# TC_masterProto_Ard.net
KiCad netlist of a schematic drawn in EAGLE
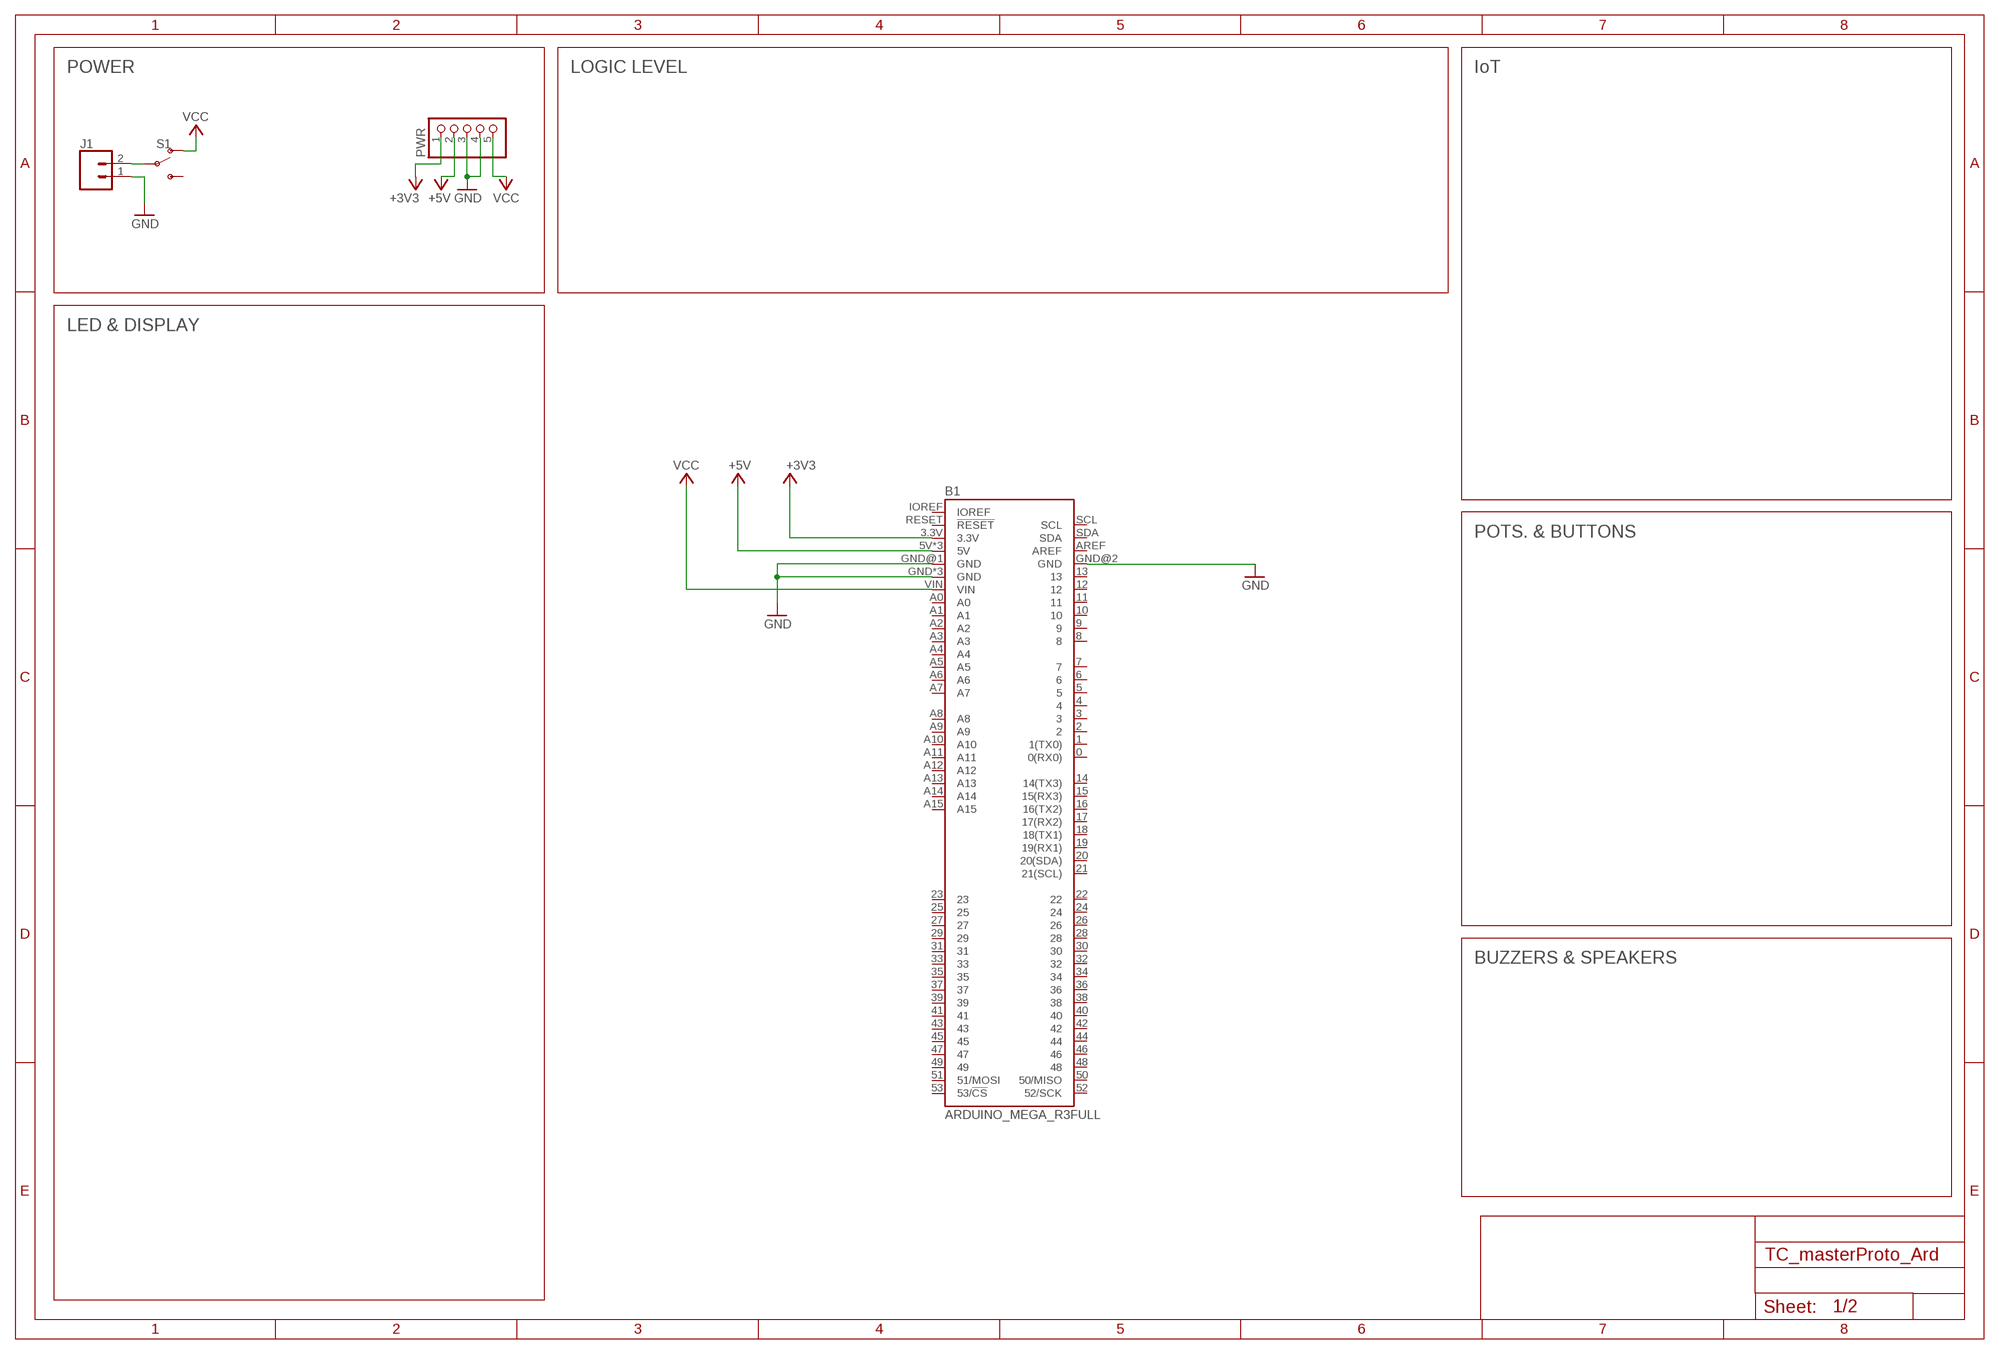
[diagram p0: schematic, sheet 1]
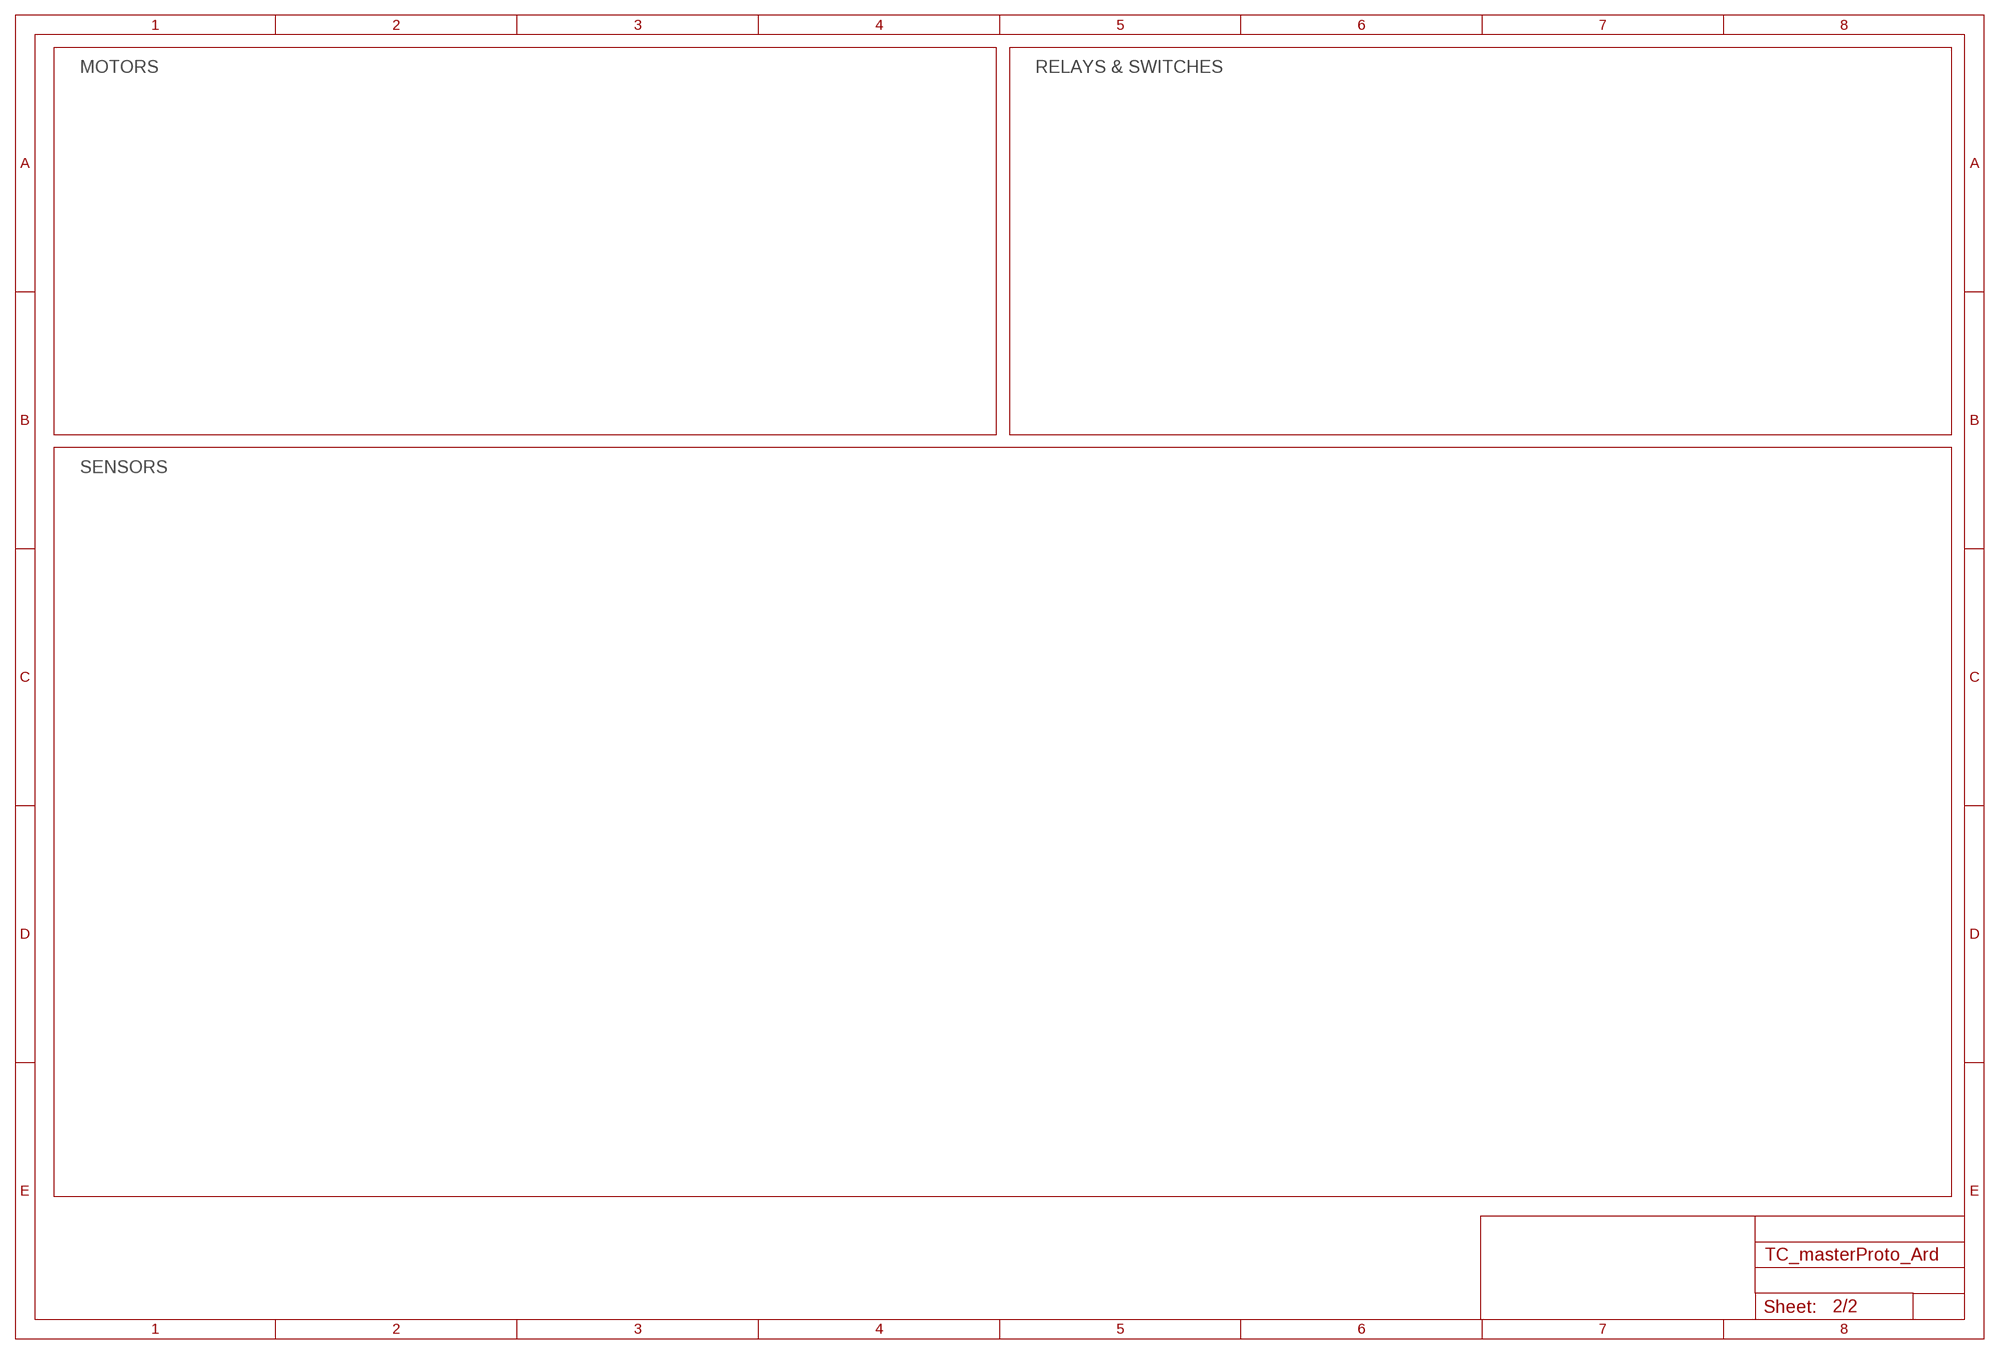
[diagram p1: schematic, sheet 2]

(export (version "E")
  (design (tool "Eeschema 10.0.6"))
  (components
    (comp (ref "B1")
      (value "ARDUINO_MEGA_R3FULL")
      (footprint "eagle-import:ARDUINO_MEGA_NO_SILK")
      (libsource (lib "eagle-import") (part "ARDUINO_MEGA_R3FULL"))
    )
    (comp (ref "J1")
      (value "CONN_023.5MM_LOCK")
      (footprint "eagle-import:SCREWTERMINAL-3.5MM-2_LOCK")
      (libsource (lib "eagle-import") (part "CONN_023.5MM_LOCK"))
    )
    (comp (ref "PWR")
      (value "PINHD-1X5")
      (footprint "eagle-import:1X05")
      (libsource (lib "eagle-import") (part "PINHD-1X5"))
    )
    (comp (ref "S1")
      (value "SWITCH-SPDT-PTH-11.6X4.0MM-LOCK")
      (footprint "eagle-import:SWITCH_SPDT_PTH_11.6X4.0MM_LOCK")
      (libsource (lib "eagle-import") (part "SWITCH-SPDT-PTH-11.6X4.0MM-LOCK"))
    )
  )
  (nets
    (net (code "1") (name "+3V3") (class "Default")
      (node (ref "B1") (pin "3.3V") (pinfunction "3.3V_3.3V") (pintype "bidirectional"))
      (node (ref "PWR") (pin "1") (pinfunction "1_1") (pintype "passive"))
    )
    (net (code "2") (name "+5V") (class "Default")
      (node (ref "B1") (pin "5V") (pinfunction "5V_5V") (pintype "bidirectional"))
      (node (ref "B1") (pin "5V@1") (pinfunction "5V_5V@1") (pintype "bidirectional"))
      (node (ref "B1") (pin "5V@2") (pinfunction "5V_5V@2") (pintype "bidirectional"))
      (node (ref "PWR") (pin "2") (pinfunction "2_2") (pintype "passive"))
    )
    (net (code "3") (name "GND") (class "Default")
      (node (ref "B1") (pin "GND") (pinfunction "GND_GND") (pintype "bidirectional"))
      (node (ref "B1") (pin "GND@1") (pinfunction "GND_GND@1") (pintype "bidirectional"))
      (node (ref "B1") (pin "GND@2") (pinfunction "GND_GND@2") (pintype "bidirectional"))
      (node (ref "B1") (pin "GND@3") (pinfunction "GND_GND@3") (pintype "bidirectional"))
      (node (ref "B1") (pin "GND@4") (pinfunction "GND_GND@4") (pintype "bidirectional"))
      (node (ref "J1") (pin "1") (pinfunction "1_1") (pintype "passive"))
      (node (ref "PWR") (pin "3") (pinfunction "3_3") (pintype "passive"))
      (node (ref "PWR") (pin "4") (pinfunction "4_4") (pintype "passive"))
    )
    (net (code "4") (name "Net-(S1-P)") (class "Default")
      (node (ref "J1") (pin "2") (pinfunction "2_2") (pintype "passive"))
      (node (ref "S1") (pin "2") (pinfunction "P_2") (pintype "passive"))
    )
    (net (code "5") (name "VCC") (class "Default")
      (node (ref "B1") (pin "VIN") (pinfunction "VIN_VIN") (pintype "bidirectional"))
      (node (ref "PWR") (pin "5") (pinfunction "5_5") (pintype "passive"))
      (node (ref "S1") (pin "1") (pinfunction "O_1") (pintype "passive"))
    )
    (net (code "6") (name "unconnected-(B1-0(RX0)-Pad0)") (class "Default")
      (node (ref "B1") (pin "0") (pinfunction "0(RX0)_0") (pintype "bidirectional"))
    )
    (net (code "7") (name "unconnected-(B1-1(TX0)-Pad1)") (class "Default")
      (node (ref "B1") (pin "1") (pinfunction "1(TX0)_1") (pintype "bidirectional"))
    )
    (net (code "8") (name "unconnected-(B1-14(TX3)-Pad14)") (class "Default")
      (node (ref "B1") (pin "14") (pinfunction "14(TX3)_14") (pintype "bidirectional"))
    )
    (net (code "9") (name "unconnected-(B1-15(RX3)-Pad15)") (class "Default")
      (node (ref "B1") (pin "15") (pinfunction "15(RX3)_15") (pintype "bidirectional"))
    )
    (net (code "10") (name "unconnected-(B1-16(TX2)-Pad16)") (class "Default")
      (node (ref "B1") (pin "16") (pinfunction "16(TX2)_16") (pintype "bidirectional"))
    )
    (net (code "11") (name "unconnected-(B1-17(RX2)-Pad17)") (class "Default")
      (node (ref "B1") (pin "17") (pinfunction "17(RX2)_17") (pintype "bidirectional"))
    )
    (net (code "12") (name "unconnected-(B1-18(TX1)-Pad18)") (class "Default")
      (node (ref "B1") (pin "18") (pinfunction "18(TX1)_18") (pintype "bidirectional"))
    )
    (net (code "13") (name "unconnected-(B1-19(RX1)-Pad19)") (class "Default")
      (node (ref "B1") (pin "19") (pinfunction "19(RX1)_19") (pintype "bidirectional"))
    )
    (net (code "14") (name "unconnected-(B1-20(SDA)-Pad20)") (class "Default")
      (node (ref "B1") (pin "20") (pinfunction "20(SDA)_20") (pintype "bidirectional"))
    )
    (net (code "15") (name "unconnected-(B1-21(SCL)-Pad21)") (class "Default")
      (node (ref "B1") (pin "21") (pinfunction "21(SCL)_21") (pintype "bidirectional"))
    )
    (net (code "16") (name "unconnected-(B1-50{slash}MISO-Pad50)") (class "Default")
      (node (ref "B1") (pin "50") (pinfunction "50/MISO_50") (pintype "bidirectional"))
    )
    (net (code "17") (name "unconnected-(B1-51{slash}MOSI-Pad51)") (class "Default")
      (node (ref "B1") (pin "51") (pinfunction "51/MOSI_51") (pintype "bidirectional"))
    )
    (net (code "18") (name "unconnected-(B1-52{slash}SCK-Pad52)") (class "Default")
      (node (ref "B1") (pin "52") (pinfunction "52/SCK_52") (pintype "bidirectional"))
    )
    (net (code "19") (name "unconnected-(B1-53{slash}~{CS}-Pad53)") (class "Default")
      (node (ref "B1") (pin "53") (pinfunction "53/~{CS}_53") (pintype "bidirectional"))
    )
    (net (code "20") (name "unconnected-(B1-Pad2)") (class "Default")
      (node (ref "B1") (pin "2") (pinfunction "2_2") (pintype "bidirectional"))
    )
    (net (code "21") (name "unconnected-(B1-Pad3)") (class "Default")
      (node (ref "B1") (pin "3") (pinfunction "3_3") (pintype "bidirectional"))
    )
    (net (code "22") (name "unconnected-(B1-Pad4)") (class "Default")
      (node (ref "B1") (pin "4") (pinfunction "4_4") (pintype "bidirectional"))
    )
    (net (code "23") (name "unconnected-(B1-Pad5)") (class "Default")
      (node (ref "B1") (pin "5") (pinfunction "5_5") (pintype "bidirectional"))
    )
    (net (code "24") (name "unconnected-(B1-Pad6)") (class "Default")
      (node (ref "B1") (pin "6") (pinfunction "6_6") (pintype "bidirectional"))
    )
    (net (code "25") (name "unconnected-(B1-Pad7)") (class "Default")
      (node (ref "B1") (pin "7") (pinfunction "7_7") (pintype "bidirectional"))
    )
    (net (code "26") (name "unconnected-(B1-Pad8)") (class "Default")
      (node (ref "B1") (pin "8") (pinfunction "8_8") (pintype "bidirectional"))
    )
    (net (code "27") (name "unconnected-(B1-Pad9)") (class "Default")
      (node (ref "B1") (pin "9") (pinfunction "9_9") (pintype "bidirectional"))
    )
    (net (code "28") (name "unconnected-(B1-Pad10)") (class "Default")
      (node (ref "B1") (pin "10") (pinfunction "10_10") (pintype "bidirectional"))
    )
    (net (code "29") (name "unconnected-(B1-Pad11)") (class "Default")
      (node (ref "B1") (pin "11") (pinfunction "11_11") (pintype "bidirectional"))
    )
    (net (code "30") (name "unconnected-(B1-Pad12)") (class "Default")
      (node (ref "B1") (pin "12") (pinfunction "12_12") (pintype "bidirectional"))
    )
    (net (code "31") (name "unconnected-(B1-Pad13)") (class "Default")
      (node (ref "B1") (pin "13") (pinfunction "13_13") (pintype "bidirectional"))
    )
    (net (code "32") (name "unconnected-(B1-Pad22)") (class "Default")
      (node (ref "B1") (pin "22") (pinfunction "22_22") (pintype "bidirectional"))
    )
    (net (code "33") (name "unconnected-(B1-Pad23)") (class "Default")
      (node (ref "B1") (pin "23") (pinfunction "23_23") (pintype "bidirectional"))
    )
    (net (code "34") (name "unconnected-(B1-Pad24)") (class "Default")
      (node (ref "B1") (pin "24") (pinfunction "24_24") (pintype "bidirectional"))
    )
    (net (code "35") (name "unconnected-(B1-Pad25)") (class "Default")
      (node (ref "B1") (pin "25") (pinfunction "25_25") (pintype "bidirectional"))
    )
    (net (code "36") (name "unconnected-(B1-Pad26)") (class "Default")
      (node (ref "B1") (pin "26") (pinfunction "26_26") (pintype "bidirectional"))
    )
    (net (code "37") (name "unconnected-(B1-Pad27)") (class "Default")
      (node (ref "B1") (pin "27") (pinfunction "27_27") (pintype "bidirectional"))
    )
    (net (code "38") (name "unconnected-(B1-Pad28)") (class "Default")
      (node (ref "B1") (pin "28") (pinfunction "28_28") (pintype "bidirectional"))
    )
    (net (code "39") (name "unconnected-(B1-Pad29)") (class "Default")
      (node (ref "B1") (pin "29") (pinfunction "29_29") (pintype "bidirectional"))
    )
    (net (code "40") (name "unconnected-(B1-Pad30)") (class "Default")
      (node (ref "B1") (pin "30") (pinfunction "30_30") (pintype "bidirectional"))
    )
    (net (code "41") (name "unconnected-(B1-Pad31)") (class "Default")
      (node (ref "B1") (pin "31") (pinfunction "31_31") (pintype "bidirectional"))
    )
    (net (code "42") (name "unconnected-(B1-Pad32)") (class "Default")
      (node (ref "B1") (pin "32") (pinfunction "32_32") (pintype "bidirectional"))
    )
    (net (code "43") (name "unconnected-(B1-Pad33)") (class "Default")
      (node (ref "B1") (pin "33") (pinfunction "33_33") (pintype "bidirectional"))
    )
    (net (code "44") (name "unconnected-(B1-Pad34)") (class "Default")
      (node (ref "B1") (pin "34") (pinfunction "34_34") (pintype "bidirectional"))
    )
    (net (code "45") (name "unconnected-(B1-Pad35)") (class "Default")
      (node (ref "B1") (pin "35") (pinfunction "35_35") (pintype "bidirectional"))
    )
    (net (code "46") (name "unconnected-(B1-Pad36)") (class "Default")
      (node (ref "B1") (pin "36") (pinfunction "36_36") (pintype "bidirectional"))
    )
    (net (code "47") (name "unconnected-(B1-Pad37)") (class "Default")
      (node (ref "B1") (pin "37") (pinfunction "37_37") (pintype "bidirectional"))
    )
    (net (code "48") (name "unconnected-(B1-Pad38)") (class "Default")
      (node (ref "B1") (pin "38") (pinfunction "38_38") (pintype "bidirectional"))
    )
    (net (code "49") (name "unconnected-(B1-Pad39)") (class "Default")
      (node (ref "B1") (pin "39") (pinfunction "39_39") (pintype "bidirectional"))
    )
    (net (code "50") (name "unconnected-(B1-Pad40)") (class "Default")
      (node (ref "B1") (pin "40") (pinfunction "40_40") (pintype "bidirectional"))
    )
    (net (code "51") (name "unconnected-(B1-Pad41)") (class "Default")
      (node (ref "B1") (pin "41") (pinfunction "41_41") (pintype "bidirectional"))
    )
    (net (code "52") (name "unconnected-(B1-Pad42)") (class "Default")
      (node (ref "B1") (pin "42") (pinfunction "42_42") (pintype "bidirectional"))
    )
    (net (code "53") (name "unconnected-(B1-Pad43)") (class "Default")
      (node (ref "B1") (pin "43") (pinfunction "43_43") (pintype "bidirectional"))
    )
    (net (code "54") (name "unconnected-(B1-Pad44)") (class "Default")
      (node (ref "B1") (pin "44") (pinfunction "44_44") (pintype "bidirectional"))
    )
    (net (code "55") (name "unconnected-(B1-Pad45)") (class "Default")
      (node (ref "B1") (pin "45") (pinfunction "45_45") (pintype "bidirectional"))
    )
    (net (code "56") (name "unconnected-(B1-Pad46)") (class "Default")
      (node (ref "B1") (pin "46") (pinfunction "46_46") (pintype "bidirectional"))
    )
    (net (code "57") (name "unconnected-(B1-Pad47)") (class "Default")
      (node (ref "B1") (pin "47") (pinfunction "47_47") (pintype "bidirectional"))
    )
    (net (code "58") (name "unconnected-(B1-Pad48)") (class "Default")
      (node (ref "B1") (pin "48") (pinfunction "48_48") (pintype "bidirectional"))
    )
    (net (code "59") (name "unconnected-(B1-Pad49)") (class "Default")
      (node (ref "B1") (pin "49") (pinfunction "49_49") (pintype "bidirectional"))
    )
    (net (code "60") (name "unconnected-(B1-PadA0)") (class "Default")
      (node (ref "B1") (pin "A0") (pinfunction "A0_A0") (pintype "bidirectional"))
    )
    (net (code "61") (name "unconnected-(B1-PadA1)") (class "Default")
      (node (ref "B1") (pin "A1") (pinfunction "A1_A1") (pintype "bidirectional"))
    )
    (net (code "62") (name "unconnected-(B1-PadA2)") (class "Default")
      (node (ref "B1") (pin "A2") (pinfunction "A2_A2") (pintype "bidirectional"))
    )
    (net (code "63") (name "unconnected-(B1-PadA3)") (class "Default")
      (node (ref "B1") (pin "A3") (pinfunction "A3_A3") (pintype "bidirectional"))
    )
    (net (code "64") (name "unconnected-(B1-PadA4)") (class "Default")
      (node (ref "B1") (pin "A4") (pinfunction "A4_A4") (pintype "bidirectional"))
    )
    (net (code "65") (name "unconnected-(B1-PadA5)") (class "Default")
      (node (ref "B1") (pin "A5") (pinfunction "A5_A5") (pintype "bidirectional"))
    )
    (net (code "66") (name "unconnected-(B1-PadA6)") (class "Default")
      (node (ref "B1") (pin "A6") (pinfunction "A6_A6") (pintype "bidirectional"))
    )
    (net (code "67") (name "unconnected-(B1-PadA7)") (class "Default")
      (node (ref "B1") (pin "A7") (pinfunction "A7_A7") (pintype "bidirectional"))
    )
    (net (code "68") (name "unconnected-(B1-PadA8)") (class "Default")
      (node (ref "B1") (pin "A8") (pinfunction "A8_A8") (pintype "bidirectional"))
    )
    (net (code "69") (name "unconnected-(B1-PadA9)") (class "Default")
      (node (ref "B1") (pin "A9") (pinfunction "A9_A9") (pintype "bidirectional"))
    )
    (net (code "70") (name "unconnected-(B1-PadA10)") (class "Default")
      (node (ref "B1") (pin "A10") (pinfunction "A10_A10") (pintype "bidirectional"))
    )
    (net (code "71") (name "unconnected-(B1-PadA11)") (class "Default")
      (node (ref "B1") (pin "A11") (pinfunction "A11_A11") (pintype "bidirectional"))
    )
    (net (code "72") (name "unconnected-(B1-PadA12)") (class "Default")
      (node (ref "B1") (pin "A12") (pinfunction "A12_A12") (pintype "bidirectional"))
    )
    (net (code "73") (name "unconnected-(B1-PadA13)") (class "Default")
      (node (ref "B1") (pin "A13") (pinfunction "A13_A13") (pintype "bidirectional"))
    )
    (net (code "74") (name "unconnected-(B1-PadA14)") (class "Default")
      (node (ref "B1") (pin "A14") (pinfunction "A14_A14") (pintype "bidirectional"))
    )
    (net (code "75") (name "unconnected-(B1-PadA15)") (class "Default")
      (node (ref "B1") (pin "A15") (pinfunction "A15_A15") (pintype "bidirectional"))
    )
    (net (code "76") (name "unconnected-(B1-PadAREF)") (class "Default")
      (node (ref "B1") (pin "AREF") (pinfunction "AREF_AREF") (pintype "bidirectional"))
    )
    (net (code "77") (name "unconnected-(B1-PadIOREF)") (class "Default")
      (node (ref "B1") (pin "IOREF") (pinfunction "IOREF_IOREF") (pintype "bidirectional"))
    )
    (net (code "78") (name "unconnected-(B1-PadSCL)") (class "Default")
      (node (ref "B1") (pin "SCL") (pinfunction "SCL_SCL") (pintype "bidirectional"))
    )
    (net (code "79") (name "unconnected-(B1-PadSDA)") (class "Default")
      (node (ref "B1") (pin "SDA") (pinfunction "SDA_SDA") (pintype "bidirectional"))
    )
    (net (code "80") (name "unconnected-(B1-~{RESET}-PadRESET)") (class "Default")
      (node (ref "B1") (pin "RESET") (pinfunction "~{RESET}_RESET") (pintype "bidirectional"))
    )
    (net (code "81") (name "unconnected-(S1-S-Pad3)") (class "Default")
      (node (ref "S1") (pin "3") (pinfunction "S_3") (pintype "passive"))
    )
  )
)
